# SD_Card_Breakout.net
KiCad netlist of a schematic drawn in Altium Designer
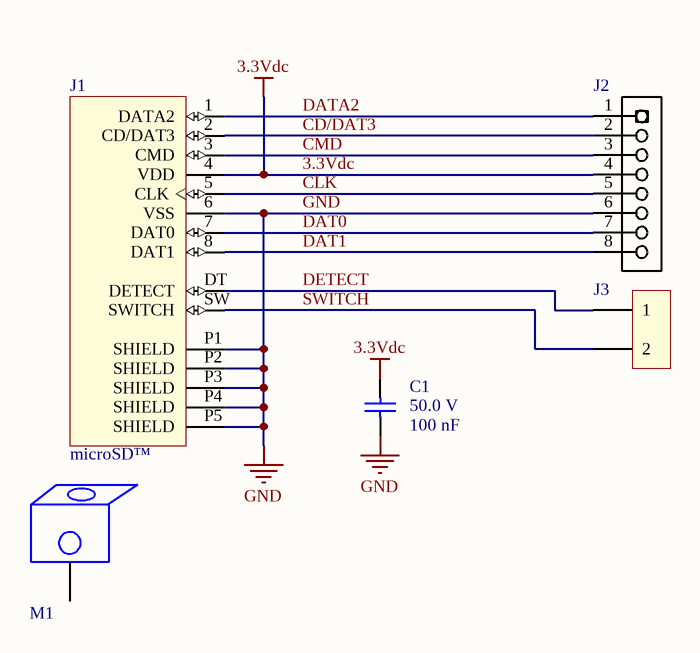
[diagram p0: SD Card Breakout.SchDoc]

(export (version "E")
  (design (tool "Eeschema 10.0.6"))
  (components
    (comp (ref "C1")
      (value "Cap")
      (footprint "Cap,0805")
      (description "Capacitor; Ceramic; Cap 0.1 uF; Tol 5%; Vol-Rtg 50 VDC; SMT; 0805; X7R; Tape & Reel")
      (fields
        (field (name "MANUFACTURER PART NUMBER") "08055C104JAT2A")
        (field (name "VOLTAGE RATING (DC)") "50.0 V")
        (field (name "CAPACITANCE") "100 nF")
      )
      (libsource (lib "Master JULY2019") (part "Cap,0805,100nf,50V,5%,08055C104JAT2A"))
    )
    (comp (ref "J1")
      (value "5031821852")
      (footprint "Conn,SD micro,503182-1852")
      (description "MICRO SD NORMAL ULTRALOWPRO8CKTE")
      (fields (field (name "MANUFACTURER") "Molex") (field (name "CARD TYPE") "microSD™"))
      (libsource (lib "Master JULY2019") (part "Conn,SD Micro,10 (8 + 2) Position,SMD,RA,5031821852"))
    )
    (comp (ref "J2")
      (value "HEADER,0.1\",8Pin,SinlgeRow")
      (footprint "Header,8Pin,SingleRow, RA,0.1\"")
      (libsource (lib "Master JULY2019") (part "HEADER,0.1{dblquote},8Pin,SinlgeRow"))
    )
    (comp (ref "J3")
      (value "Generic Header")
      (footprint "HEADER-1X2,0.1\",RA1")
      (libsource (lib "Master JULY2019") (part "Header 1x2,0.1{dblquote}Spacing"))
    )
    (comp (ref "M1")
      (value "4334")
      (footprint "Mech,Bracket,RA,#6,Threaded")
      (description "Mounting Bracket Short L #6-32 (2) Steel, Nickel Plated")
      (fields (field (name "MANUFACTURER") "Keystone Electronics"))
      (libsource (lib "Master JULY2019") (part "Mech,Bracket,RA,Threaded,4334"))
    )
  )
  (nets
    (net (code "1") (name "/CD{slash}DAT3") (class "Default")
      (node (ref "J1") (pin "2") (pinfunction "CD/DAT3_2") (pintype "bidirectional"))
      (node (ref "J2") (pin "2") (pintype "passive"))
    )
    (net (code "2") (name "/CLK") (class "Default")
      (node (ref "J1") (pin "5") (pinfunction "CLK_5") (pintype "bidirectional"))
      (node (ref "J2") (pin "5") (pintype "passive"))
    )
    (net (code "3") (name "/CMD") (class "Default")
      (node (ref "J1") (pin "3") (pinfunction "CMD_3") (pintype "bidirectional"))
      (node (ref "J2") (pin "3") (pintype "passive"))
    )
    (net (code "4") (name "/DAT0") (class "Default")
      (node (ref "J1") (pin "7") (pinfunction "DAT0_7") (pintype "bidirectional"))
      (node (ref "J2") (pin "7") (pintype "passive"))
    )
    (net (code "5") (name "/DAT1") (class "Default")
      (node (ref "J1") (pin "8") (pinfunction "DAT1_8") (pintype "bidirectional"))
      (node (ref "J2") (pin "8") (pintype "passive"))
    )
    (net (code "6") (name "/DATA2") (class "Default")
      (node (ref "J1") (pin "1") (pinfunction "DATA2_1") (pintype "bidirectional"))
      (node (ref "J2") (pin "1") (pintype "passive"))
    )
    (net (code "7") (name "/DETECT") (class "Default")
      (node (ref "J1") (pin "DT") (pinfunction "DETECT_DT") (pintype "bidirectional"))
      (node (ref "J3") (pin "1") (pinfunction "1_1") (pintype "passive"))
    )
    (net (code "8") (name "/SWITCH") (class "Default")
      (node (ref "J1") (pin "SW") (pinfunction "SWITCH_SW") (pintype "bidirectional"))
      (node (ref "J3") (pin "2") (pinfunction "2_2") (pintype "passive"))
    )
    (net (code "9") (name "3.3Vdc") (class "Default")
      (node (ref "C1") (pin "2") (pinfunction "2_2") (pintype "passive"))
      (node (ref "J1") (pin "4") (pinfunction "VDD_4") (pintype "power_in"))
      (node (ref "J2") (pin "4") (pintype "passive"))
    )
    (net (code "10") (name "GND") (class "Default")
      (node (ref "C1") (pin "1") (pinfunction "1_1") (pintype "passive"))
      (node (ref "J1") (pin "6") (pinfunction "VSS_6") (pintype "power_in"))
      (node (ref "J1") (pin "P1") (pinfunction "SHIELD_P1") (pintype "passive"))
      (node (ref "J1") (pin "P2") (pinfunction "SHIELD_P2") (pintype "passive"))
      (node (ref "J1") (pin "P3") (pinfunction "SHIELD_P3") (pintype "passive"))
      (node (ref "J1") (pin "P4") (pinfunction "SHIELD_P4") (pintype "passive"))
      (node (ref "J1") (pin "P5") (pinfunction "SHIELD_P5") (pintype "passive"))
      (node (ref "J2") (pin "6") (pintype "passive"))
    )
    (net (code "11") (name "unconnected-(M1-Pad1)") (class "Default")
      (node (ref "M1") (pin "1") (pinfunction "1_1") (pintype "passive"))
    )
  )
)
